# RX-Super-Regenerative-1Transistor-Elekto.net
KiCad netlist of a schematic drawn in EAGLE
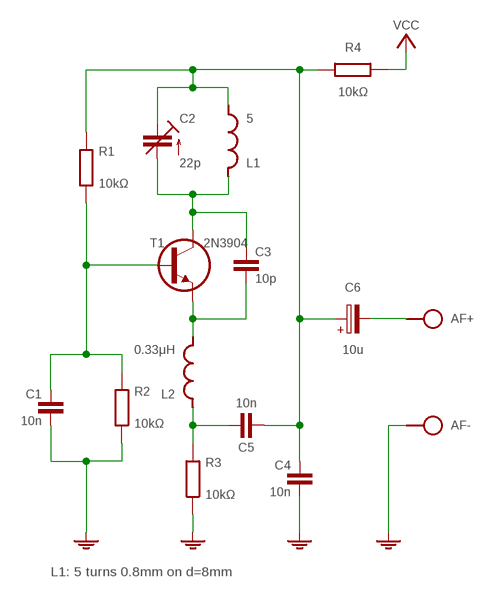
[diagram p0: schematic, sheet 1]

(export (version "E")
  (design (tool "Eeschema 10.0.6"))
  (components
    (comp (ref "AF+")
      (value "SPAD")
      (footprint "eagle-import:SPAD")
      (libsource (lib "eagle-import") (part "SPAD"))
    )
    (comp (ref "AF-")
      (value "SPAD")
      (footprint "eagle-import:SPAD")
      (libsource (lib "eagle-import") (part "SPAD"))
    )
    (comp (ref "C1")
      (value "10n")
      (footprint "eagle-import:C050-020X036_V")
      (libsource (lib "eagle-import") (part "C050-020X036/V"))
    )
    (comp (ref "C2")
      (value "22p")
      (footprint "eagle-import:TRIM-2222-808")
      (libsource (lib "eagle-import") (part "C-TR-PH20127"))
    )
    (comp (ref "C3")
      (value "10p")
      (footprint "eagle-import:C050-020X036_V")
      (libsource (lib "eagle-import") (part "C050-020X036/V"))
    )
    (comp (ref "C4")
      (value "10n")
      (footprint "eagle-import:C025-024X044")
      (libsource (lib "eagle-import") (part "C025-024X044"))
    )
    (comp (ref "C5")
      (value "10n")
      (footprint "eagle-import:C050-020X036")
      (libsource (lib "eagle-import") (part "C-H050-020X036"))
    )
    (comp (ref "C6")
      (value "10u")
      (footprint "eagle-import:E2,5-3")
      (libsource (lib "eagle-import") (part "CPOLE2,5-3"))
    )
    (comp (ref "L1")
      (value "5")
      (footprint "eagle-import:L-04-5_5V-X")
      (libsource (lib "eagle-import") (part "L-SHORTL-04-5/5V-X"))
    )
    (comp (ref "L2")
      (value "0.33μH")
      (footprint "eagle-import:L-02_7V")
      (libsource (lib "eagle-import") (part "L-SHORT02/7V"))
    )
    (comp (ref "R1")
      (value "10kΩ")
      (footprint "eagle-import:0204_10")
      (libsource (lib "eagle-import") (part "R0204/10"))
    )
    (comp (ref "R2")
      (value "10kΩ")
      (footprint "eagle-import:0204_10")
      (libsource (lib "eagle-import") (part "R0204/10"))
    )
    (comp (ref "R3")
      (value "10kΩ")
      (footprint "eagle-import:0204_10")
      (libsource (lib "eagle-import") (part "R0204/10"))
    )
    (comp (ref "R4")
      (value "10kΩ")
      (footprint "eagle-import:0204_7")
      (libsource (lib "eagle-import") (part "R0204/7"))
    )
    (comp (ref "S1")
      (value "VCC_GNDPWR-L")
      (footprint "eagle-import:PWR-L")
      (libsource (lib "eagle-import") (part "VCC_GNDPWR-L"))
    )
    (comp (ref "T1")
      (value "2N3904")
      (footprint "eagle-import:TO92")
      (libsource (lib "eagle-import") (part "2N3904"))
    )
  )
  (nets
    (net (code "1") (name "GND") (class "Default")
      (node (ref "AF-") (pin "1") (pinfunction "P$1_1") (pintype "passive"))
      (node (ref "C1") (pin "2") (pinfunction "2_2") (pintype "passive"))
      (node (ref "C4") (pin "2") (pinfunction "2_2") (pintype "passive"))
      (node (ref "R2") (pin "1") (pinfunction "1_1") (pintype "passive"))
      (node (ref "R3") (pin "1") (pinfunction "1_1") (pintype "passive"))
      (node (ref "S1") (pin "1") (pinfunction "GND_1") (pintype "power_in"))
    )
    (net (code "2") (name "Net-(AF+-P$1)") (class "Default")
      (node (ref "AF+") (pin "1") (pinfunction "P$1_1") (pintype "passive"))
      (node (ref "C6") (pin "-") (pinfunction "-_-") (pintype "passive"))
    )
    (net (code "3") (name "Net-(C2-A)") (class "Default")
      (node (ref "C2") (pin "2") (pinfunction "A_2") (pintype "passive"))
      (node (ref "C3") (pin "1") (pinfunction "1_1") (pintype "passive"))
      (node (ref "L1") (pin "2") (pinfunction "2_2") (pintype "passive"))
      (node (ref "T1") (pin "3") (pinfunction "C_3") (pintype "passive"))
    )
    (net (code "4") (name "Net-(C2-E-Pad1)") (class "Default")
      (node (ref "C2") (pin "1") (pinfunction "E_1") (pintype "passive"))
      (node (ref "C2") (pin "3") (pinfunction "E_3") (pintype "passive"))
      (node (ref "C4") (pin "1") (pinfunction "1_1") (pintype "passive"))
      (node (ref "C5") (pin "1") (pinfunction "1_1") (pintype "passive"))
      (node (ref "C6") (pin "+") (pinfunction "+_+") (pintype "passive"))
      (node (ref "L1") (pin "1") (pinfunction "1_1") (pintype "passive"))
      (node (ref "R1") (pin "2") (pinfunction "2_2") (pintype "passive"))
      (node (ref "R4") (pin "2") (pinfunction "2_2") (pintype "passive"))
    )
    (net (code "5") (name "Net-(C5-Pad2)") (class "Default")
      (node (ref "C5") (pin "2") (pinfunction "2_2") (pintype "passive"))
      (node (ref "L2") (pin "2") (pinfunction "2_2") (pintype "passive"))
      (node (ref "R3") (pin "2") (pinfunction "2_2") (pintype "passive"))
    )
    (net (code "6") (name "Net-(S1A-VCC)") (class "Default")
      (node (ref "R4") (pin "1") (pinfunction "1_1") (pintype "passive"))
      (node (ref "S1") (pin "2") (pinfunction "VCC_2") (pintype "power_in"))
    )
    (net (code "7") (name "Net-(T1-B)") (class "Default")
      (node (ref "C1") (pin "1") (pinfunction "1_1") (pintype "passive"))
      (node (ref "R1") (pin "1") (pinfunction "1_1") (pintype "passive"))
      (node (ref "R2") (pin "2") (pinfunction "2_2") (pintype "passive"))
      (node (ref "T1") (pin "2") (pinfunction "B_2") (pintype "passive"))
    )
    (net (code "8") (name "Net-(T1-E)") (class "Default")
      (node (ref "C3") (pin "2") (pinfunction "2_2") (pintype "passive"))
      (node (ref "L2") (pin "1") (pinfunction "1_1") (pintype "passive"))
      (node (ref "T1") (pin "1") (pinfunction "E_1") (pintype "passive"))
    )
  )
)
